# BackBreaker_CustomHardware.net
KiCad netlist of a schematic drawn in EAGLE
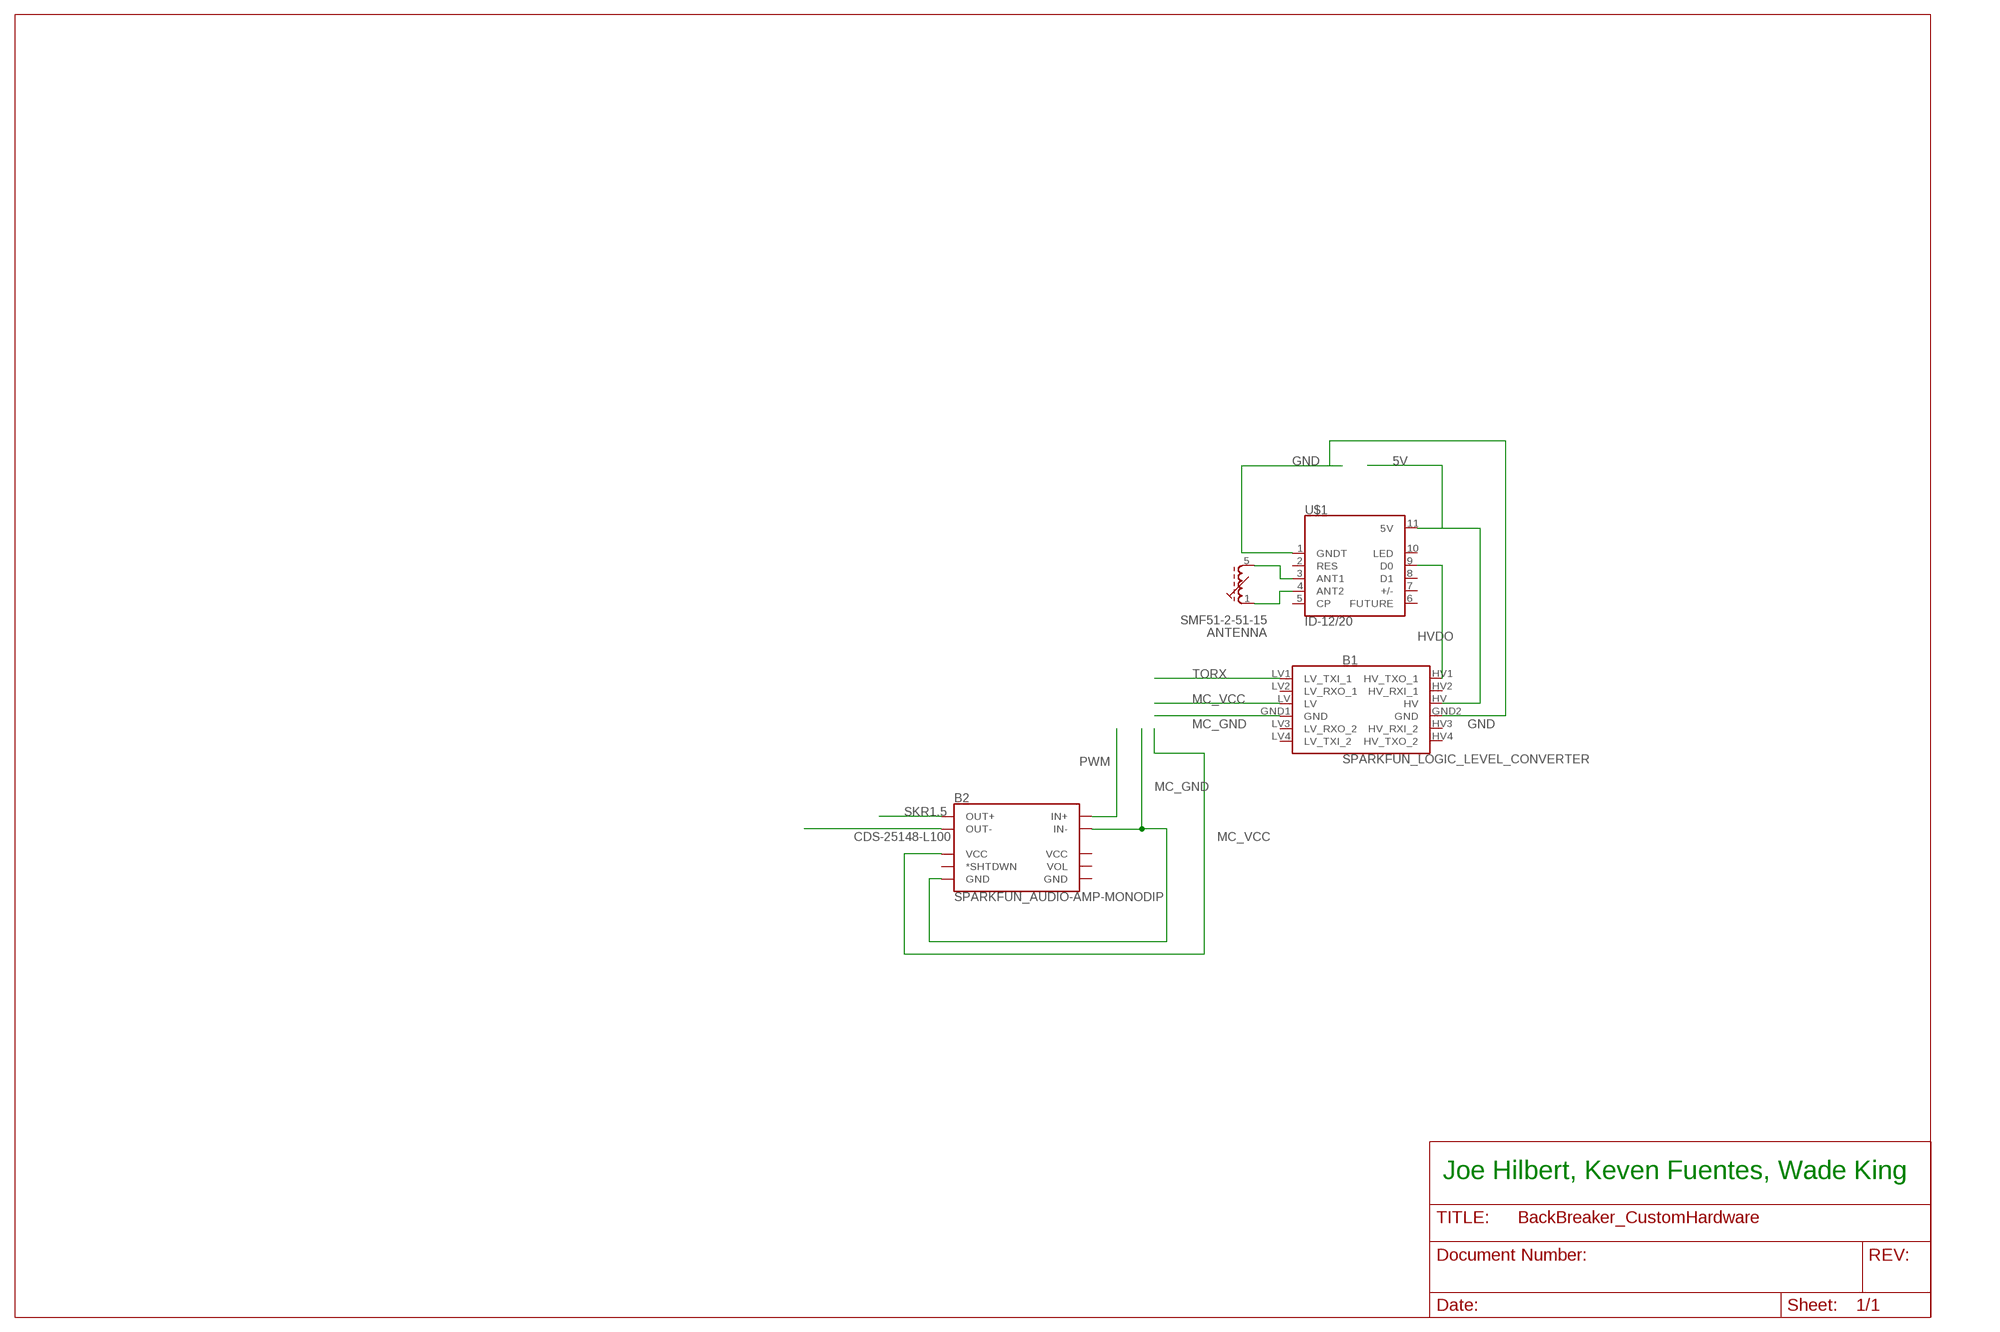
[diagram p0: schematic, sheet 1]

(export (version "E")
  (design (tool "Eeschema 10.0.6"))
  (components
    (comp (ref "ANTENNA")
      (value "SMF51-2-51-15")
      (footprint "eagle-import:SMF5_1")
      (libsource (lib "eagle-import") (part "SMF51-2-51-15"))
    )
    (comp (ref "B1")
      (value "SPARKFUN_LOGIC_LEVEL_CONVERTER")
      (footprint "eagle-import:SPARKFUN_LOGIC_LEVEL_CONVERTER")
      (libsource (lib "eagle-import") (part "SPARKFUN_LOGIC_LEVEL_CONVERTER"))
    )
    (comp (ref "B2")
      (value "SPARKFUN_AUDIO-AMP-MONODIP")
      (footprint "eagle-import:AUDIO-AMP-MONO")
      (libsource (lib "eagle-import") (part "SPARKFUN_AUDIO-AMP-MONODIP"))
    )
    (comp (ref "U$1")
      (value "ID-12/20")
      (footprint "eagle-import:ID-12")
      (libsource (lib "eagle-import") (part "ID-12/20"))
    )
  )
  (nets
    (net (code "1") (name "/5V") (class "Default")
      (node (ref "B1") (pin "HV") (pinfunction "HV_HV") (pintype "power_in"))
      (node (ref "U$1") (pin "11") (pinfunction "5V_11") (pintype "bidirectional"))
    )
    (net (code "2") (name "/CDS-25148-L100") (class "Default")
      (node (ref "B2") (pin "OUT-") (pinfunction "OUT-_OUT-") (pintype "bidirectional"))
    )
    (net (code "3") (name "/GND") (class "Default")
      (node (ref "B1") (pin "GND2") (pinfunction "GND_GND2") (pintype "power_in"))
      (node (ref "U$1") (pin "1") (pinfunction "GNDT_1") (pintype "bidirectional"))
    )
    (net (code "4") (name "/HVDO") (class "Default")
      (node (ref "B1") (pin "HV1") (pinfunction "HV_TXO_1_HV1") (pintype "bidirectional"))
      (node (ref "U$1") (pin "9") (pinfunction "D0_9") (pintype "bidirectional"))
    )
    (net (code "5") (name "/MC_GND") (class "Default")
      (node (ref "B1") (pin "GND1") (pinfunction "GND_GND1") (pintype "power_in"))
      (node (ref "B2") (pin "IN-") (pinfunction "IN-_IN-") (pintype "bidirectional"))
      (node (ref "B2") (pin "PWR-") (pinfunction "GND_PWR-") (pintype "bidirectional"))
    )
    (net (code "6") (name "/MC_VCC") (class "Default")
      (node (ref "B1") (pin "LV") (pinfunction "LV_LV") (pintype "power_in"))
      (node (ref "B2") (pin "PWR+") (pinfunction "VCC_PWR+") (pintype "bidirectional"))
    )
    (net (code "7") (name "/PWM") (class "Default")
      (node (ref "B2") (pin "IN+") (pinfunction "IN+_IN+") (pintype "bidirectional"))
    )
    (net (code "8") (name "/SKR1.5") (class "Default")
      (node (ref "B2") (pin "OUT+") (pinfunction "OUT+_OUT+") (pintype "bidirectional"))
    )
    (net (code "9") (name "/TORX") (class "Default")
      (node (ref "B1") (pin "LV1") (pinfunction "LV_TXI_1_LV1") (pintype "bidirectional"))
    )
    (net (code "10") (name "Net-(ANTENNAA-A)") (class "Default")
      (node (ref "ANTENNA") (pin "1") (pinfunction "A_1") (pintype "passive"))
      (node (ref "U$1") (pin "4") (pinfunction "ANT2_4") (pintype "bidirectional"))
    )
    (net (code "11") (name "Net-(ANTENNAA-E)") (class "Default")
      (node (ref "ANTENNA") (pin "5") (pinfunction "E_5") (pintype "passive"))
      (node (ref "U$1") (pin "3") (pinfunction "ANT1_3") (pintype "bidirectional"))
    )
    (net (code "12") (name "unconnected-(B1-HV_RXI_1-PadHV2)") (class "Default")
      (node (ref "B1") (pin "HV2") (pinfunction "HV_RXI_1_HV2") (pintype "bidirectional"))
    )
    (net (code "13") (name "unconnected-(B1-HV_RXI_2-PadHV3)") (class "Default")
      (node (ref "B1") (pin "HV3") (pinfunction "HV_RXI_2_HV3") (pintype "bidirectional"))
    )
    (net (code "14") (name "unconnected-(B1-HV_TXO_2-PadHV4)") (class "Default")
      (node (ref "B1") (pin "HV4") (pinfunction "HV_TXO_2_HV4") (pintype "bidirectional"))
    )
    (net (code "15") (name "unconnected-(B1-LV_RXO_1-PadLV2)") (class "Default")
      (node (ref "B1") (pin "LV2") (pinfunction "LV_RXO_1_LV2") (pintype "bidirectional"))
    )
    (net (code "16") (name "unconnected-(B1-LV_RXO_2-PadLV3)") (class "Default")
      (node (ref "B1") (pin "LV3") (pinfunction "LV_RXO_2_LV3") (pintype "bidirectional"))
    )
    (net (code "17") (name "unconnected-(B1-LV_TXI_2-PadLV4)") (class "Default")
      (node (ref "B1") (pin "LV4") (pinfunction "LV_TXI_2_LV4") (pintype "bidirectional"))
    )
    (net (code "18") (name "unconnected-(B2-*SHTDWN-PadS)") (class "Default")
      (node (ref "B2") (pin "S") (pinfunction "*SHTDWN_S") (pintype "bidirectional"))
    )
    (net (code "19") (name "unconnected-(B2-GND-PadVOL-)") (class "Default")
      (node (ref "B2") (pin "VOL-") (pinfunction "GND_VOL-") (pintype "bidirectional"))
    )
    (net (code "20") (name "unconnected-(B2-PadVOL)") (class "Default")
      (node (ref "B2") (pin "VOL") (pinfunction "VOL_VOL") (pintype "bidirectional"))
    )
    (net (code "21") (name "unconnected-(B2-VCC-PadVOL+)") (class "Default")
      (node (ref "B2") (pin "VOL+") (pinfunction "VCC_VOL+") (pintype "bidirectional"))
    )
    (net (code "22") (name "unconnected-(U$1-+{slash}--Pad7)") (class "Default")
      (node (ref "U$1") (pin "7") (pinfunction "+/-_7") (pintype "bidirectional"))
    )
    (net (code "23") (name "unconnected-(U$1-CP-Pad5)") (class "Default")
      (node (ref "U$1") (pin "5") (pinfunction "CP_5") (pintype "bidirectional"))
    )
    (net (code "24") (name "unconnected-(U$1-D1-Pad8)") (class "Default")
      (node (ref "U$1") (pin "8") (pinfunction "D1_8") (pintype "bidirectional"))
    )
    (net (code "25") (name "unconnected-(U$1-FUTURE-Pad6)") (class "Default")
      (node (ref "U$1") (pin "6") (pinfunction "FUTURE_6") (pintype "bidirectional"))
    )
    (net (code "26") (name "unconnected-(U$1-LED-Pad10)") (class "Default")
      (node (ref "U$1") (pin "10") (pinfunction "LED_10") (pintype "bidirectional"))
    )
    (net (code "27") (name "unconnected-(U$1-RES-Pad2)") (class "Default")
      (node (ref "U$1") (pin "2") (pinfunction "RES_2") (pintype "bidirectional"))
    )
  )
)
